# buffer.net
KiCad netlist of a schematic drawn in EAGLE
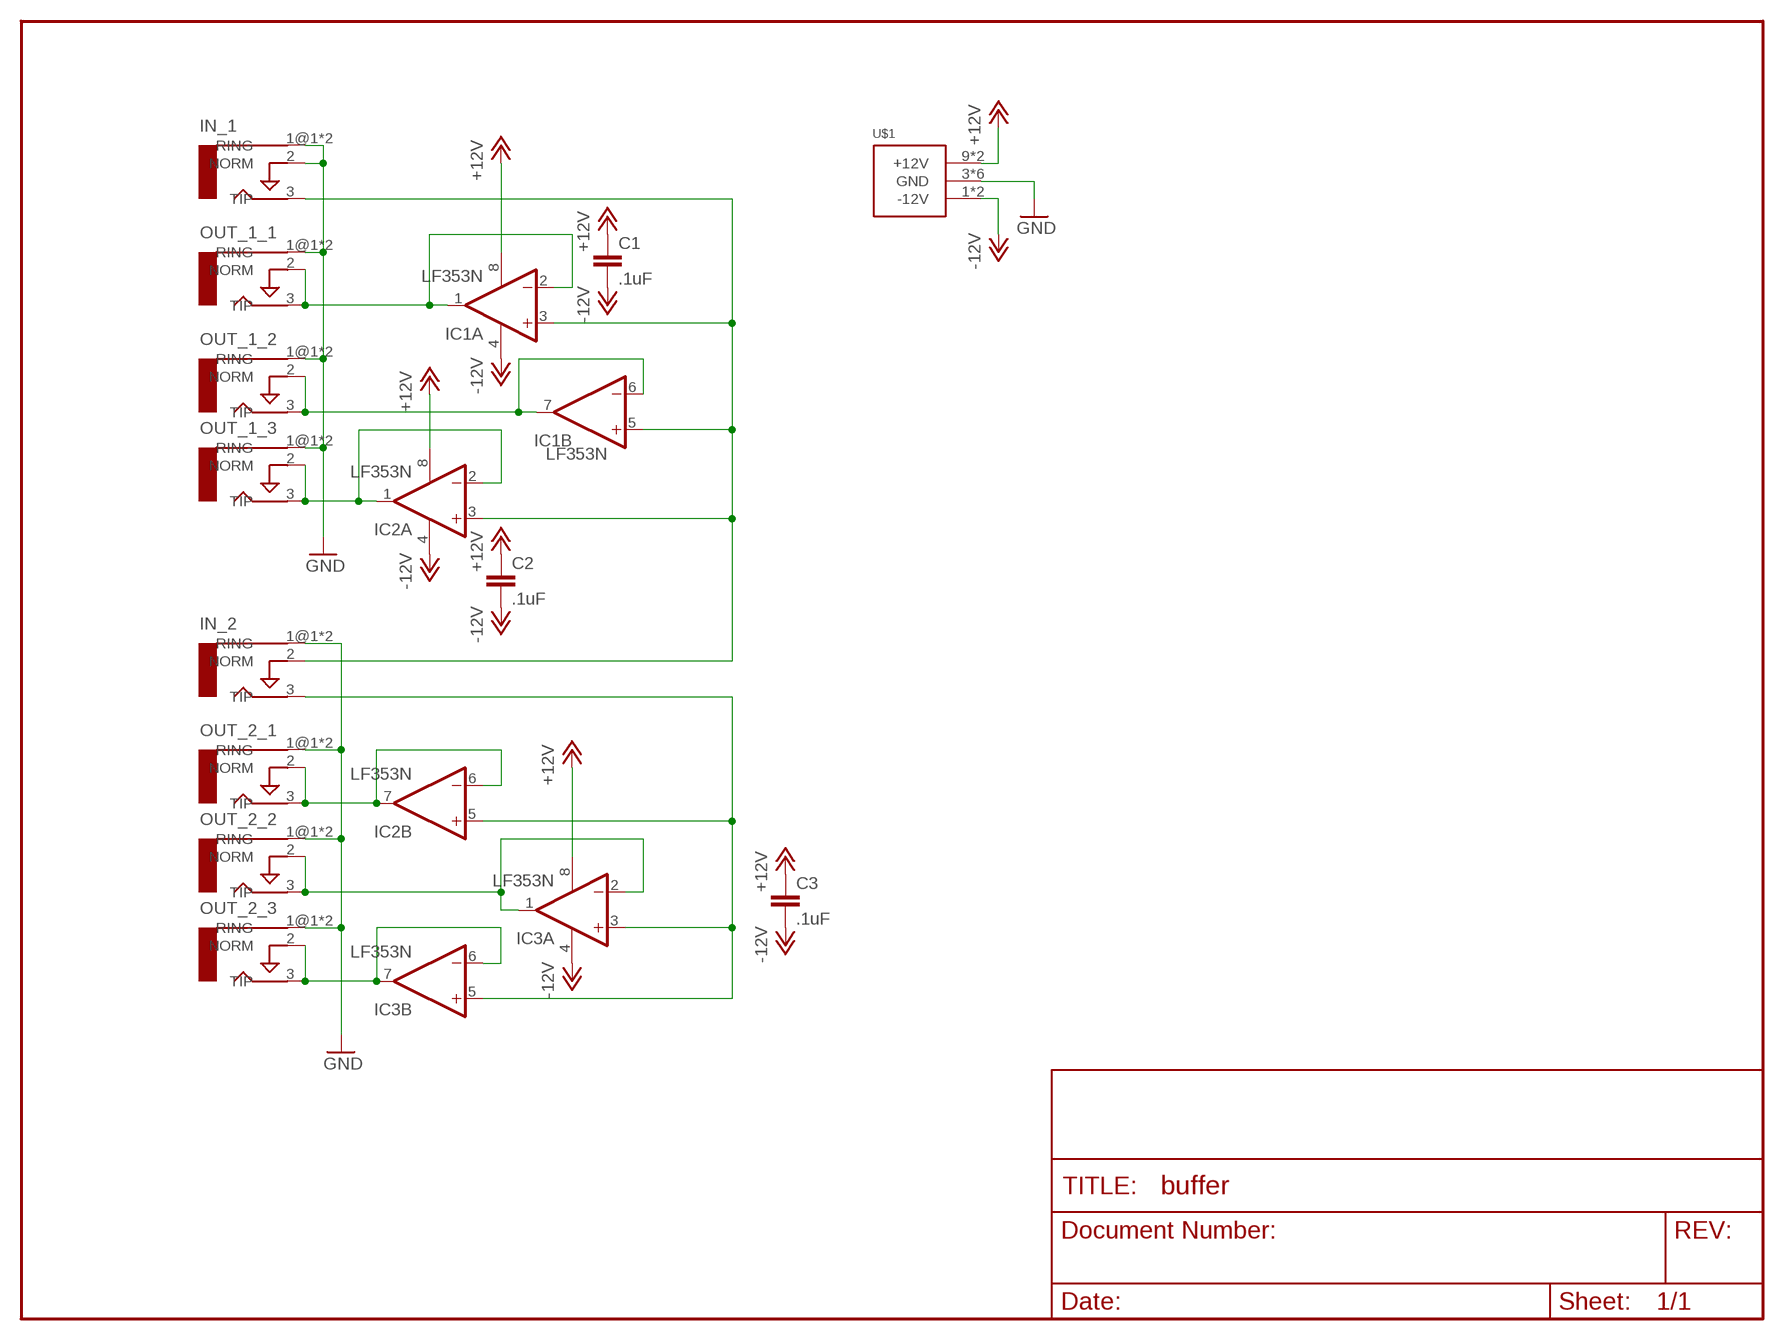
[diagram p0: schematic, sheet 1]

(export (version "E")
  (design (tool "Eeschema 10.0.6"))
  (components
    (comp (ref "C1")
      (value ".1uF")
      (footprint "eagle-import:CAP-PTH-SMALL")
      (libsource (lib "eagle-import") (part "CAPPTH"))
    )
    (comp (ref "C2")
      (value ".1uF")
      (footprint "eagle-import:CAP-PTH-SMALL")
      (libsource (lib "eagle-import") (part "CAPPTH"))
    )
    (comp (ref "C3")
      (value ".1uF")
      (footprint "eagle-import:CAP-PTH-SMALL")
      (libsource (lib "eagle-import") (part "CAPPTH"))
    )
    (comp (ref "IC1")
      (value "LF353N")
      (footprint "eagle-import:DIL08")
      (libsource (lib "eagle-import") (part "LF353N"))
    )
    (comp (ref "IC2")
      (value "LF353N")
      (footprint "eagle-import:DIL08")
      (libsource (lib "eagle-import") (part "LF353N"))
    )
    (comp (ref "IC3")
      (value "LF353N")
      (footprint "eagle-import:DIL08")
      (libsource (lib "eagle-import") (part "LF353N"))
    )
    (comp (ref "IN_1")
      (value "AUDIO-JACKERTHENVAR")
      (footprint "eagle-import:ERTHENVAR-JACK")
      (libsource (lib "eagle-import") (part "AUDIO-JACKERTHENVAR"))
    )
    (comp (ref "IN_2")
      (value "AUDIO-JACKERTHENVAR")
      (footprint "eagle-import:ERTHENVAR-JACK")
      (libsource (lib "eagle-import") (part "AUDIO-JACKERTHENVAR"))
    )
    (comp (ref "OUT_1_1")
      (value "AUDIO-JACKERTHENVAR")
      (footprint "eagle-import:ERTHENVAR-JACK")
      (libsource (lib "eagle-import") (part "AUDIO-JACKERTHENVAR"))
    )
    (comp (ref "OUT_1_2")
      (value "AUDIO-JACKERTHENVAR")
      (footprint "eagle-import:ERTHENVAR-JACK")
      (libsource (lib "eagle-import") (part "AUDIO-JACKERTHENVAR"))
    )
    (comp (ref "OUT_1_3")
      (value "AUDIO-JACKERTHENVAR")
      (footprint "eagle-import:ERTHENVAR-JACK")
      (libsource (lib "eagle-import") (part "AUDIO-JACKERTHENVAR"))
    )
    (comp (ref "OUT_2_1")
      (value "AUDIO-JACKERTHENVAR")
      (footprint "eagle-import:ERTHENVAR-JACK")
      (libsource (lib "eagle-import") (part "AUDIO-JACKERTHENVAR"))
    )
    (comp (ref "OUT_2_2")
      (value "AUDIO-JACKERTHENVAR")
      (footprint "eagle-import:ERTHENVAR-JACK")
      (libsource (lib "eagle-import") (part "AUDIO-JACKERTHENVAR"))
    )
    (comp (ref "OUT_2_3")
      (value "AUDIO-JACKERTHENVAR")
      (footprint "eagle-import:ERTHENVAR-JACK")
      (libsource (lib "eagle-import") (part "AUDIO-JACKERTHENVAR"))
    )
    (comp (ref "U$1")
      (value "POWER_SIMPLE16")
      (footprint "eagle-import:POWER_16")
      (libsource (lib "eagle-import") (part "POWER_SIMPLE16"))
    )
  )
  (nets
    (net (code "1") (name "+12V") (class "Default")
      (node (ref "C1") (pin "1") (pinfunction "1_1") (pintype "passive"))
      (node (ref "C2") (pin "1") (pinfunction "1_1") (pintype "passive"))
      (node (ref "C3") (pin "1") (pinfunction "1_1") (pintype "passive"))
      (node (ref "IC1") (pin "8") (pinfunction "V+_8") (pintype "power_in"))
      (node (ref "IC2") (pin "8") (pinfunction "V+_8") (pintype "power_in"))
      (node (ref "IC3") (pin "8") (pinfunction "V+_8") (pintype "power_in"))
      (node (ref "U$1") (pin "10") (pinfunction "+12V_10") (pintype "bidirectional"))
      (node (ref "U$1") (pin "9") (pinfunction "+12V_9") (pintype "bidirectional"))
    )
    (net (code "2") (name "-12V") (class "Default")
      (node (ref "C1") (pin "2") (pinfunction "2_2") (pintype "passive"))
      (node (ref "C2") (pin "2") (pinfunction "2_2") (pintype "passive"))
      (node (ref "C3") (pin "2") (pinfunction "2_2") (pintype "passive"))
      (node (ref "IC1") (pin "4") (pinfunction "V-_4") (pintype "power_in"))
      (node (ref "IC2") (pin "4") (pinfunction "V-_4") (pintype "power_in"))
      (node (ref "IC3") (pin "4") (pinfunction "V-_4") (pintype "power_in"))
      (node (ref "U$1") (pin "1") (pinfunction "-12V_1") (pintype "bidirectional"))
      (node (ref "U$1") (pin "2") (pinfunction "-12V_2") (pintype "bidirectional"))
    )
    (net (code "3") (name "GND") (class "Default")
      (node (ref "IN_1") (pin "1@1") (pinfunction "RING_1@1") (pintype "bidirectional"))
      (node (ref "IN_1") (pin "1@2") (pinfunction "RING_1@2") (pintype "bidirectional"))
      (node (ref "IN_1") (pin "2") (pinfunction "NORM_2") (pintype "bidirectional"))
      (node (ref "IN_2") (pin "1@1") (pinfunction "RING_1@1") (pintype "bidirectional"))
      (node (ref "IN_2") (pin "1@2") (pinfunction "RING_1@2") (pintype "bidirectional"))
      (node (ref "OUT_1_1") (pin "1@1") (pinfunction "RING_1@1") (pintype "bidirectional"))
      (node (ref "OUT_1_1") (pin "1@2") (pinfunction "RING_1@2") (pintype "bidirectional"))
      (node (ref "OUT_1_2") (pin "1@1") (pinfunction "RING_1@1") (pintype "bidirectional"))
      (node (ref "OUT_1_2") (pin "1@2") (pinfunction "RING_1@2") (pintype "bidirectional"))
      (node (ref "OUT_1_3") (pin "1@1") (pinfunction "RING_1@1") (pintype "bidirectional"))
      (node (ref "OUT_1_3") (pin "1@2") (pinfunction "RING_1@2") (pintype "bidirectional"))
      (node (ref "OUT_2_1") (pin "1@1") (pinfunction "RING_1@1") (pintype "bidirectional"))
      (node (ref "OUT_2_1") (pin "1@2") (pinfunction "RING_1@2") (pintype "bidirectional"))
      (node (ref "OUT_2_2") (pin "1@1") (pinfunction "RING_1@1") (pintype "bidirectional"))
      (node (ref "OUT_2_2") (pin "1@2") (pinfunction "RING_1@2") (pintype "bidirectional"))
      (node (ref "OUT_2_3") (pin "1@1") (pinfunction "RING_1@1") (pintype "bidirectional"))
      (node (ref "OUT_2_3") (pin "1@2") (pinfunction "RING_1@2") (pintype "bidirectional"))
      (node (ref "U$1") (pin "3") (pinfunction "GND_3") (pintype "bidirectional"))
      (node (ref "U$1") (pin "4") (pinfunction "GND_4") (pintype "bidirectional"))
      (node (ref "U$1") (pin "5") (pinfunction "GND_5") (pintype "bidirectional"))
      (node (ref "U$1") (pin "6") (pinfunction "GND_6") (pintype "bidirectional"))
      (node (ref "U$1") (pin "7") (pinfunction "GND_7") (pintype "bidirectional"))
      (node (ref "U$1") (pin "8") (pinfunction "GND_8") (pintype "bidirectional"))
    )
    (net (code "4") (name "Net-(IC1A-+IN)") (class "Default")
      (node (ref "IC1") (pin "3") (pinfunction "+IN_3") (pintype "input"))
      (node (ref "IC1") (pin "5") (pinfunction "+IN_5") (pintype "input"))
      (node (ref "IC2") (pin "3") (pinfunction "+IN_3") (pintype "input"))
      (node (ref "IN_1") (pin "3") (pinfunction "TIP_3") (pintype "bidirectional"))
      (node (ref "IN_2") (pin "2") (pinfunction "NORM_2") (pintype "bidirectional"))
    )
    (net (code "5") (name "Net-(IC1A--IN)") (class "Default")
      (node (ref "IC1") (pin "1") (pinfunction "OUT_1") (pintype "output"))
      (node (ref "IC1") (pin "2") (pinfunction "-IN_2") (pintype "input"))
      (node (ref "OUT_1_1") (pin "2") (pinfunction "NORM_2") (pintype "bidirectional"))
      (node (ref "OUT_1_1") (pin "3") (pinfunction "TIP_3") (pintype "bidirectional"))
    )
    (net (code "6") (name "Net-(IC1B--IN)") (class "Default")
      (node (ref "IC1") (pin "6") (pinfunction "-IN_6") (pintype "input"))
      (node (ref "IC1") (pin "7") (pinfunction "OUT_7") (pintype "output"))
      (node (ref "OUT_1_2") (pin "2") (pinfunction "NORM_2") (pintype "bidirectional"))
      (node (ref "OUT_1_2") (pin "3") (pinfunction "TIP_3") (pintype "bidirectional"))
    )
    (net (code "7") (name "Net-(IC2A--IN)") (class "Default")
      (node (ref "IC2") (pin "1") (pinfunction "OUT_1") (pintype "output"))
      (node (ref "IC2") (pin "2") (pinfunction "-IN_2") (pintype "input"))
      (node (ref "OUT_1_3") (pin "2") (pinfunction "NORM_2") (pintype "bidirectional"))
      (node (ref "OUT_1_3") (pin "3") (pinfunction "TIP_3") (pintype "bidirectional"))
    )
    (net (code "8") (name "Net-(IC2B-+IN)") (class "Default")
      (node (ref "IC2") (pin "5") (pinfunction "+IN_5") (pintype "input"))
      (node (ref "IC3") (pin "3") (pinfunction "+IN_3") (pintype "input"))
      (node (ref "IC3") (pin "5") (pinfunction "+IN_5") (pintype "input"))
      (node (ref "IN_2") (pin "3") (pinfunction "TIP_3") (pintype "bidirectional"))
    )
    (net (code "9") (name "Net-(IC2B--IN)") (class "Default")
      (node (ref "IC2") (pin "6") (pinfunction "-IN_6") (pintype "input"))
      (node (ref "IC2") (pin "7") (pinfunction "OUT_7") (pintype "output"))
      (node (ref "OUT_2_1") (pin "2") (pinfunction "NORM_2") (pintype "bidirectional"))
      (node (ref "OUT_2_1") (pin "3") (pinfunction "TIP_3") (pintype "bidirectional"))
    )
    (net (code "10") (name "Net-(IC3A--IN)") (class "Default")
      (node (ref "IC3") (pin "1") (pinfunction "OUT_1") (pintype "output"))
      (node (ref "IC3") (pin "2") (pinfunction "-IN_2") (pintype "input"))
      (node (ref "OUT_2_2") (pin "2") (pinfunction "NORM_2") (pintype "bidirectional"))
      (node (ref "OUT_2_2") (pin "3") (pinfunction "TIP_3") (pintype "bidirectional"))
    )
    (net (code "11") (name "Net-(IC3B--IN)") (class "Default")
      (node (ref "IC3") (pin "6") (pinfunction "-IN_6") (pintype "input"))
      (node (ref "IC3") (pin "7") (pinfunction "OUT_7") (pintype "output"))
      (node (ref "OUT_2_3") (pin "2") (pinfunction "NORM_2") (pintype "bidirectional"))
      (node (ref "OUT_2_3") (pin "3") (pinfunction "TIP_3") (pintype "bidirectional"))
    )
  )
)
